# Sheet1.net
KiCad netlist of a schematic drawn in Altium Designer
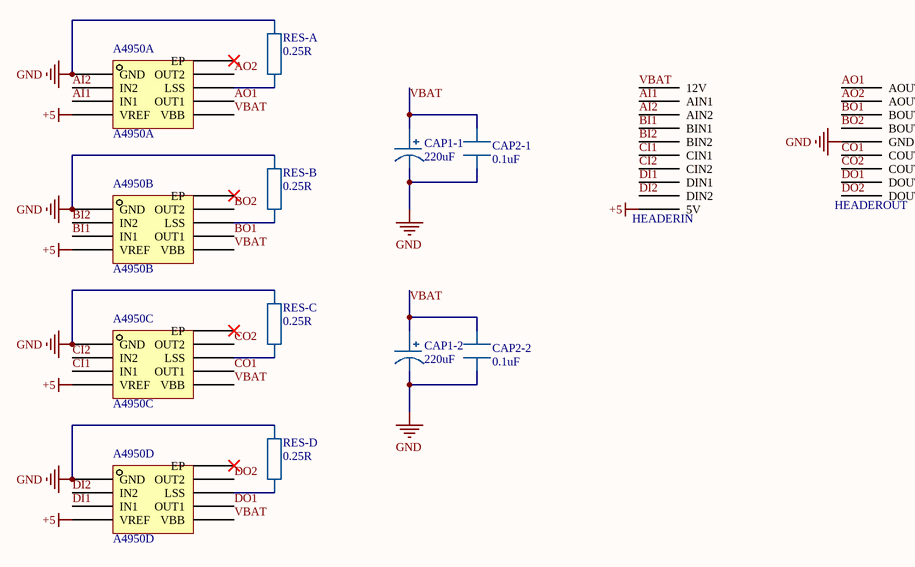
[diagram p0: Sheet1.SchDoc]

(export (version "E")
  (design (tool "Eeschema 10.0.6"))
  (components
    (comp (ref "A4950A") (value "A4950A") (footprint "A4950") (libsource (lib "Schlib0") (part "A4950")))
    (comp (ref "A4950B") (value "A4950B") (footprint "A4950") (libsource (lib "Schlib0") (part "A4950")))
    (comp (ref "A4950C") (value "A4950C") (footprint "A4950") (libsource (lib "Schlib0") (part "A4950")))
    (comp (ref "A4950D") (value "A4950D") (footprint "A4950") (libsource (lib "Schlib0") (part "A4950")))
    (comp (ref "CAP1-1") (value "220uF") (footprint "CAP1") (libsource (lib "Schlib0") (part "CAP1")))
    (comp (ref "CAP1-2") (value "220uF") (footprint "CAP1") (libsource (lib "Schlib0") (part "CAP1")))
    (comp (ref "CAP2-1") (value "0.1uF") (footprint "CAP2") (libsource (lib "Schlib0") (part "CAP2")))
    (comp (ref "CAP2-2") (value "0.1uF") (footprint "CAP2") (libsource (lib "Schlib0") (part "CAP2")))
    (comp (ref "HEADERIN")
      (value "HEADERIN")
      (footprint "HEADERIN")
      (libsource (lib "Schlib0") (part "HEADERIN"))
    )
    (comp (ref "HEADEROUT")
      (value "HEADEROUT")
      (footprint "HEADEROUT")
      (libsource (lib "Schlib0") (part "HEADEROUT"))
    )
    (comp (ref "RES-A") (value "0.25R") (footprint "RES2512") (libsource (lib "Schlib0") (part "RES")))
    (comp (ref "RES-B") (value "0.25R") (footprint "RES2512") (libsource (lib "Schlib0") (part "RES")))
    (comp (ref "RES-C") (value "0.25R") (footprint "RES2512") (libsource (lib "Schlib0") (part "RES")))
    (comp (ref "RES-D") (value "0.25R") (footprint "RES2512") (libsource (lib "Schlib0") (part "RES")))
  )
  (nets
    (net (code "1") (name "+5") (class "Default")
      (node (ref "A4950A") (pin "VREF") (pinfunction "VREF_VREF") (pintype "passive"))
      (node (ref "A4950B") (pin "VREF") (pinfunction "VREF_VREF") (pintype "passive"))
      (node (ref "A4950C") (pin "VREF") (pinfunction "VREF_VREF") (pintype "passive"))
      (node (ref "A4950D") (pin "VREF") (pinfunction "VREF_VREF") (pintype "passive"))
      (node (ref "HEADERIN") (pin "5V") (pinfunction "5V_5V") (pintype "passive"))
    )
    (net (code "2") (name "/AI1") (class "Default")
      (node (ref "A4950A") (pin "IN1") (pinfunction "IN1_IN1") (pintype "passive"))
      (node (ref "HEADERIN") (pin "AIN1") (pinfunction "AIN1_AIN1") (pintype "passive"))
    )
    (net (code "3") (name "/AI2") (class "Default")
      (node (ref "A4950A") (pin "IN2") (pinfunction "IN2_IN2") (pintype "passive"))
      (node (ref "HEADERIN") (pin "AIN2") (pinfunction "AIN2_AIN2") (pintype "passive"))
    )
    (net (code "4") (name "/AO1") (class "Default")
      (node (ref "A4950A") (pin "OUT1") (pinfunction "OUT1_OUT1") (pintype "passive"))
      (node (ref "HEADEROUT") (pin "AOUT1") (pinfunction "AOUT1_AOUT1") (pintype "passive"))
    )
    (net (code "5") (name "/AO2") (class "Default")
      (node (ref "A4950A") (pin "OUT2") (pinfunction "OUT2_OUT2") (pintype "passive"))
      (node (ref "HEADEROUT") (pin "AOUT2") (pinfunction "AOUT2_AOUT2") (pintype "passive"))
    )
    (net (code "6") (name "/BI1") (class "Default")
      (node (ref "A4950B") (pin "IN1") (pinfunction "IN1_IN1") (pintype "passive"))
      (node (ref "HEADERIN") (pin "BIN1") (pinfunction "BIN1_BIN1") (pintype "passive"))
    )
    (net (code "7") (name "/BI2") (class "Default")
      (node (ref "A4950B") (pin "IN2") (pinfunction "IN2_IN2") (pintype "passive"))
      (node (ref "HEADERIN") (pin "BIN2") (pinfunction "BIN2_BIN2") (pintype "passive"))
    )
    (net (code "8") (name "/BO1") (class "Default")
      (node (ref "A4950B") (pin "OUT1") (pinfunction "OUT1_OUT1") (pintype "passive"))
      (node (ref "HEADEROUT") (pin "BOUT1") (pinfunction "BOUT1_BOUT1") (pintype "passive"))
    )
    (net (code "9") (name "/BO2") (class "Default")
      (node (ref "A4950B") (pin "OUT2") (pinfunction "OUT2_OUT2") (pintype "passive"))
      (node (ref "HEADEROUT") (pin "BOUT2") (pinfunction "BOUT2_BOUT2") (pintype "passive"))
    )
    (net (code "10") (name "/CI1") (class "Default")
      (node (ref "A4950C") (pin "IN1") (pinfunction "IN1_IN1") (pintype "passive"))
      (node (ref "HEADERIN") (pin "CIN1") (pinfunction "CIN1_CIN1") (pintype "passive"))
    )
    (net (code "11") (name "/CI2") (class "Default")
      (node (ref "A4950C") (pin "IN2") (pinfunction "IN2_IN2") (pintype "passive"))
      (node (ref "HEADERIN") (pin "CIN2") (pinfunction "CIN2_CIN2") (pintype "passive"))
    )
    (net (code "12") (name "/CO1") (class "Default")
      (node (ref "A4950C") (pin "OUT1") (pinfunction "OUT1_OUT1") (pintype "passive"))
      (node (ref "HEADEROUT") (pin "COUT1") (pinfunction "COUT1_COUT1") (pintype "passive"))
    )
    (net (code "13") (name "/CO2") (class "Default")
      (node (ref "A4950C") (pin "OUT2") (pinfunction "OUT2_OUT2") (pintype "passive"))
      (node (ref "HEADEROUT") (pin "COUT2") (pinfunction "COUT2_COUT2") (pintype "passive"))
    )
    (net (code "14") (name "/DI1") (class "Default")
      (node (ref "A4950D") (pin "IN1") (pinfunction "IN1_IN1") (pintype "passive"))
      (node (ref "HEADERIN") (pin "DIN1") (pinfunction "DIN1_DIN1") (pintype "passive"))
    )
    (net (code "15") (name "/DI2") (class "Default")
      (node (ref "A4950D") (pin "IN2") (pinfunction "IN2_IN2") (pintype "passive"))
      (node (ref "HEADERIN") (pin "DIN2") (pinfunction "DIN2_DIN2") (pintype "passive"))
    )
    (net (code "16") (name "/DO1") (class "Default")
      (node (ref "A4950D") (pin "OUT1") (pinfunction "OUT1_OUT1") (pintype "passive"))
      (node (ref "HEADEROUT") (pin "DOUT1") (pinfunction "DOUT1_DOUT1") (pintype "passive"))
    )
    (net (code "17") (name "/DO2") (class "Default")
      (node (ref "A4950D") (pin "OUT2") (pinfunction "OUT2_OUT2") (pintype "passive"))
      (node (ref "HEADEROUT") (pin "DOUT2") (pinfunction "DOUT2_DOUT2") (pintype "passive"))
    )
    (net (code "18") (name "/VBAT") (class "Default")
      (node (ref "A4950A") (pin "VBB") (pinfunction "VBB_VBB") (pintype "passive"))
      (node (ref "A4950B") (pin "VBB") (pinfunction "VBB_VBB") (pintype "passive"))
      (node (ref "A4950C") (pin "VBB") (pinfunction "VBB_VBB") (pintype "passive"))
      (node (ref "A4950D") (pin "VBB") (pinfunction "VBB_VBB") (pintype "passive"))
      (node (ref "CAP1-1") (pin "C+") (pinfunction "C+_C+") (pintype "passive"))
      (node (ref "CAP1-2") (pin "C+") (pinfunction "C+_C+") (pintype "passive"))
      (node (ref "CAP2-1") (pin "C2") (pinfunction "C2_C2") (pintype "passive"))
      (node (ref "CAP2-2") (pin "C2") (pinfunction "C2_C2") (pintype "passive"))
      (node (ref "HEADERIN") (pin "12V") (pinfunction "12V_12V") (pintype "passive"))
    )
    (net (code "19") (name "GND") (class "Default")
      (node (ref "A4950A") (pin "GND") (pinfunction "GND_GND") (pintype "passive"))
      (node (ref "A4950B") (pin "GND") (pinfunction "GND_GND") (pintype "passive"))
      (node (ref "A4950C") (pin "GND") (pinfunction "GND_GND") (pintype "passive"))
      (node (ref "A4950D") (pin "GND") (pinfunction "GND_GND") (pintype "passive"))
      (node (ref "CAP1-1") (pin "C-") (pinfunction "C-_C-") (pintype "passive"))
      (node (ref "CAP1-2") (pin "C-") (pinfunction "C-_C-") (pintype "passive"))
      (node (ref "CAP2-1") (pin "C1") (pinfunction "C1_C1") (pintype "passive"))
      (node (ref "CAP2-2") (pin "C1") (pinfunction "C1_C1") (pintype "passive"))
      (node (ref "HEADEROUT") (pin "GND") (pinfunction "GND_GND") (pintype "passive"))
      (node (ref "RES-A") (pin "R2") (pinfunction "R2_R2") (pintype "passive"))
      (node (ref "RES-B") (pin "R2") (pinfunction "R2_R2") (pintype "passive"))
      (node (ref "RES-C") (pin "R2") (pinfunction "R2_R2") (pintype "passive"))
      (node (ref "RES-D") (pin "R2") (pinfunction "R2_R2") (pintype "passive"))
    )
    (net (code "20") (name "Net-(A4950A-PadLSS)") (class "Default")
      (node (ref "A4950A") (pin "LSS") (pinfunction "LSS_LSS") (pintype "passive"))
      (node (ref "RES-A") (pin "R1") (pinfunction "R1_R1") (pintype "passive"))
    )
    (net (code "21") (name "Net-(A4950B-PadLSS)") (class "Default")
      (node (ref "A4950B") (pin "LSS") (pinfunction "LSS_LSS") (pintype "passive"))
      (node (ref "RES-B") (pin "R1") (pinfunction "R1_R1") (pintype "passive"))
    )
    (net (code "22") (name "Net-(A4950C-PadLSS)") (class "Default")
      (node (ref "A4950C") (pin "LSS") (pinfunction "LSS_LSS") (pintype "passive"))
      (node (ref "RES-C") (pin "R1") (pinfunction "R1_R1") (pintype "passive"))
    )
    (net (code "23") (name "Net-(A4950D-PadLSS)") (class "Default")
      (node (ref "A4950D") (pin "LSS") (pinfunction "LSS_LSS") (pintype "passive"))
      (node (ref "RES-D") (pin "R1") (pinfunction "R1_R1") (pintype "passive"))
    )
    (net (code "24") (name "unconnected-(A4950A-PadEP)") (class "Default")
      (node (ref "A4950A") (pin "EP") (pinfunction "EP_EP") (pintype "passive+no_connect"))
    )
    (net (code "25") (name "unconnected-(A4950B-PadEP)") (class "Default")
      (node (ref "A4950B") (pin "EP") (pinfunction "EP_EP") (pintype "passive+no_connect"))
    )
    (net (code "26") (name "unconnected-(A4950C-PadEP)") (class "Default")
      (node (ref "A4950C") (pin "EP") (pinfunction "EP_EP") (pintype "passive+no_connect"))
    )
    (net (code "27") (name "unconnected-(A4950D-PadEP)") (class "Default")
      (node (ref "A4950D") (pin "EP") (pinfunction "EP_EP") (pintype "passive+no_connect"))
    )
  )
)
